# RJ45_Sheet.net
KiCad netlist of a schematic drawn in Altium Designer
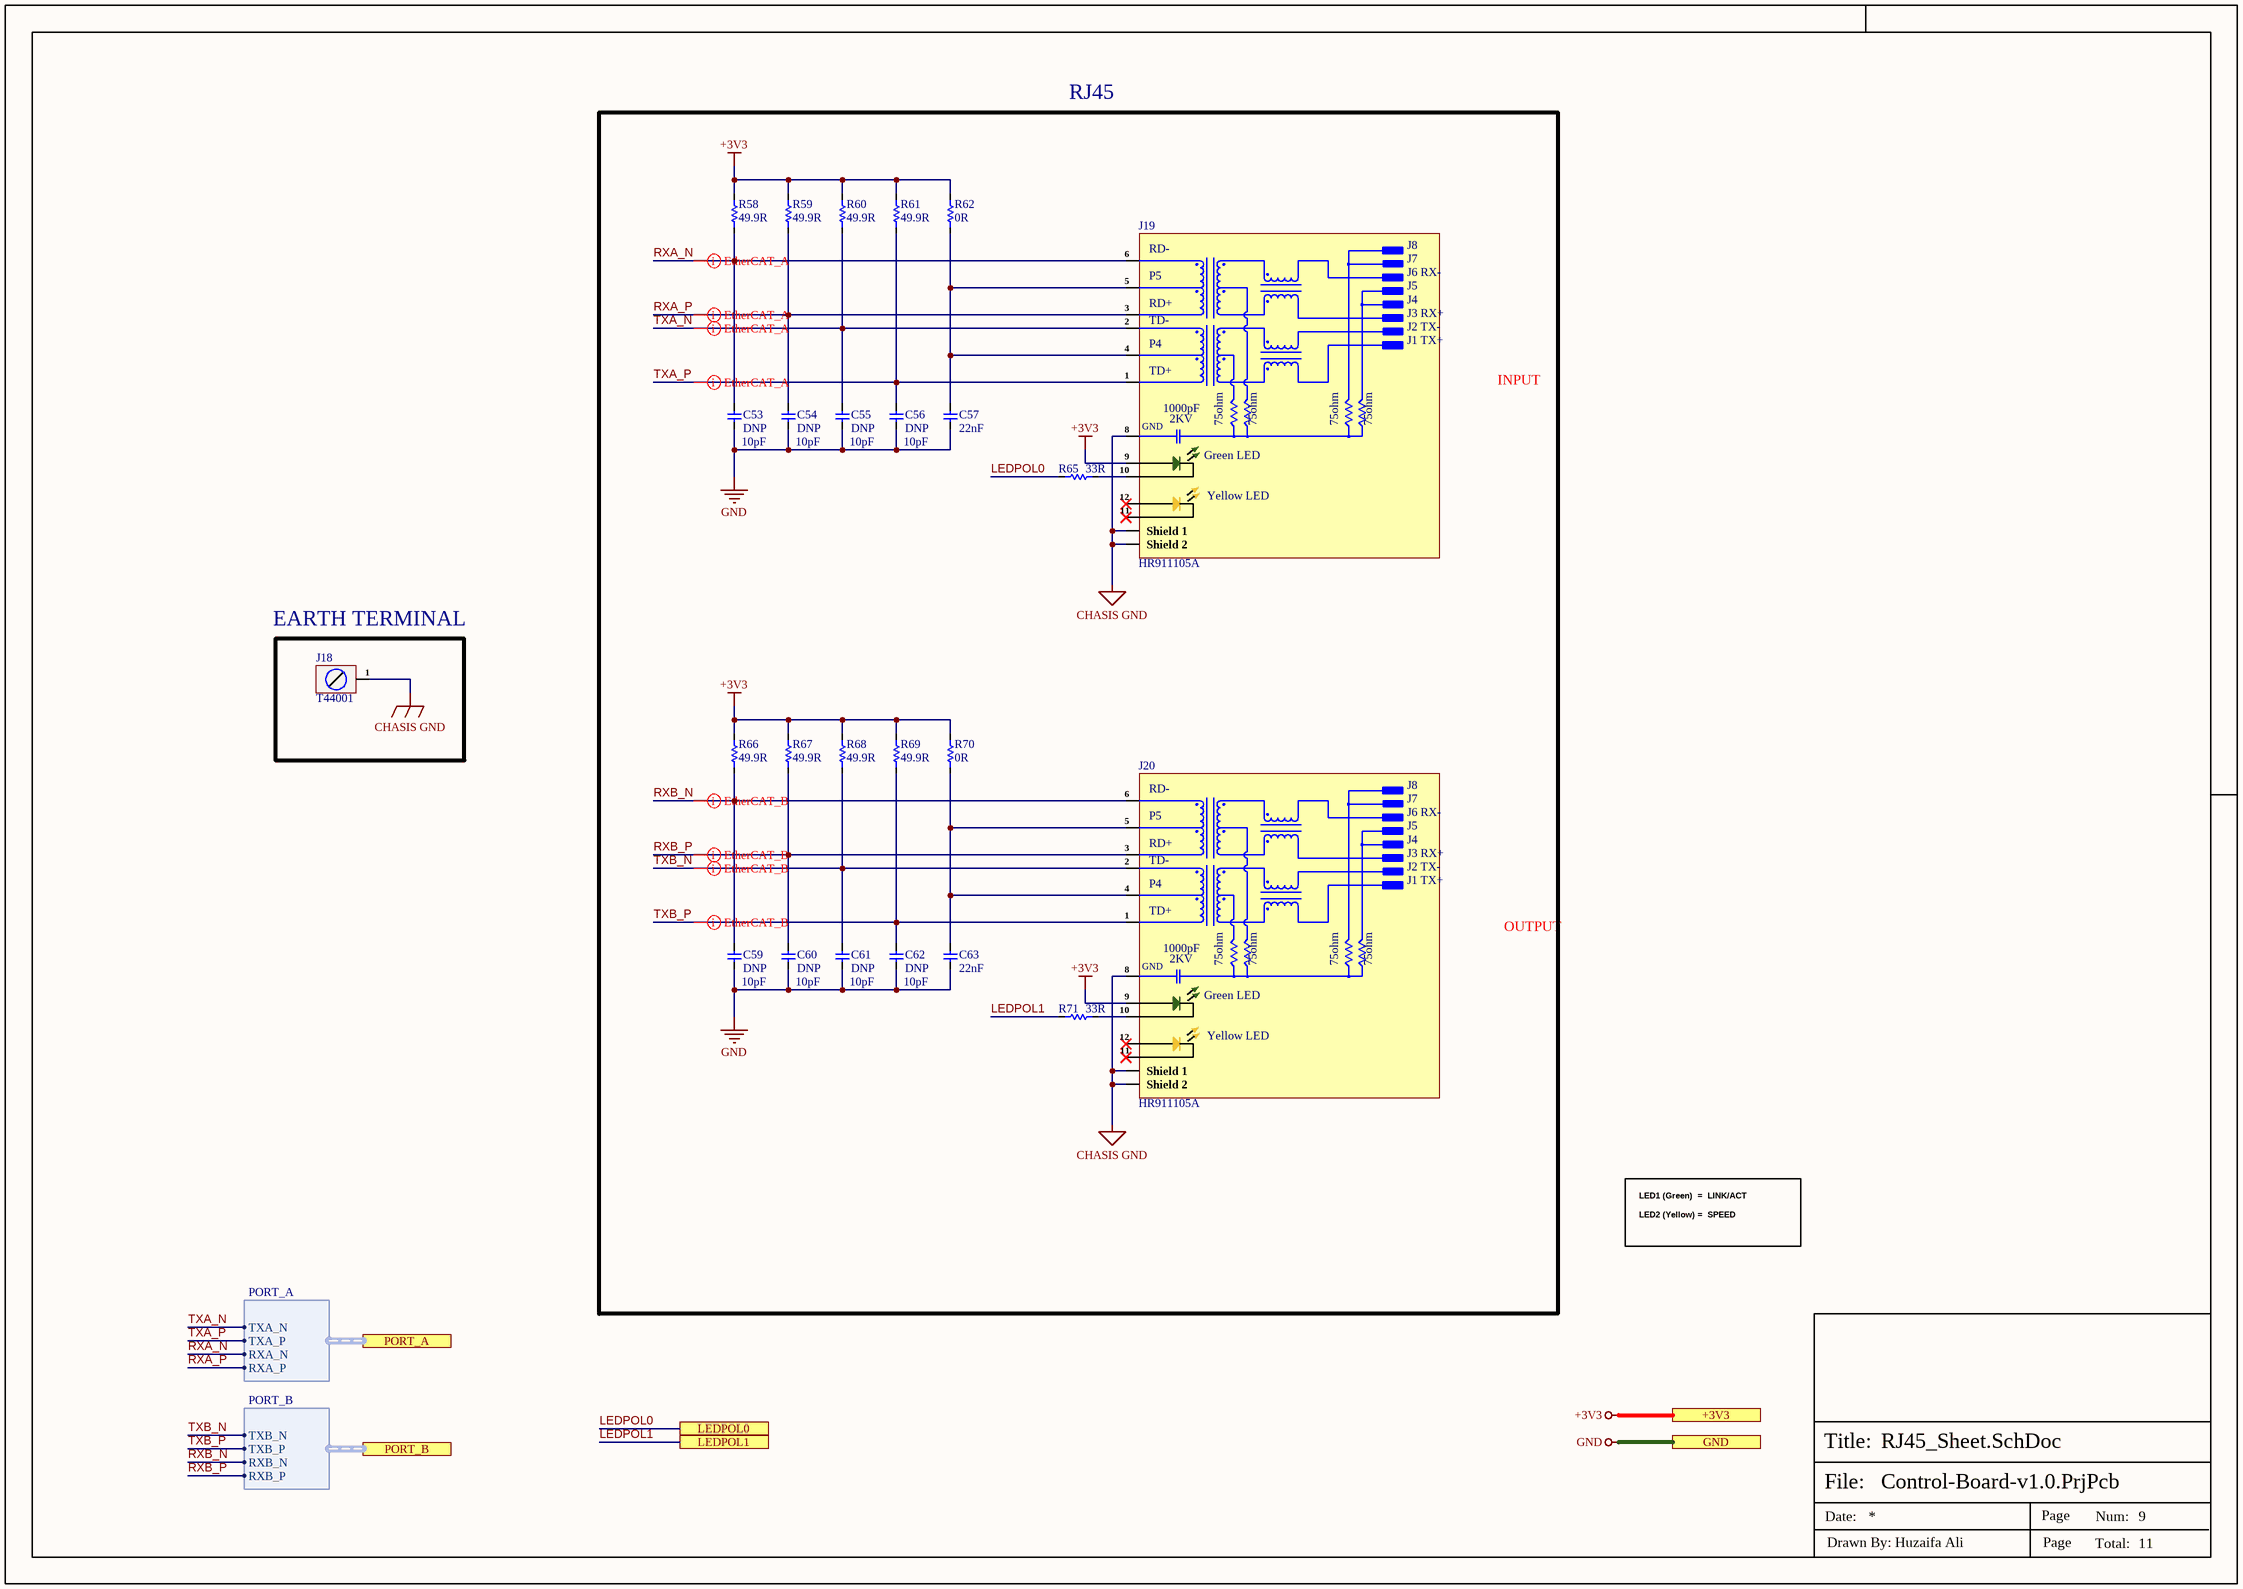
[diagram p0: RJ45_Sheet.SchDoc]

(export (version "E")
  (design (tool "Eeschema 10.0.6"))
  (components
    (comp (ref "C53")
      (value "DNP")
      (footprint "Cap-0402")
      (description "CAP CER 10PF 50V C0G/NP0 0402")
      (fields
        (field (name "MANUFACTURER") "Murata")
        (field (name "MANUFACTURER PART NUMBER") "GRM1555C1H100JA01D")
      )
      (libsource (lib "eSpark Libraries") (part "GRM1555C1H100JA01D"))
    )
    (comp (ref "C54")
      (value "DNP")
      (footprint "Cap-0402")
      (description "CAP CER 10PF 50V C0G/NP0 0402")
      (fields
        (field (name "MANUFACTURER") "Murata")
        (field (name "MANUFACTURER PART NUMBER") "GRM1555C1H100JA01D")
      )
      (libsource (lib "eSpark Libraries") (part "GRM1555C1H100JA01D"))
    )
    (comp (ref "C55")
      (value "DNP")
      (footprint "Cap-0402")
      (description "CAP CER 10PF 50V C0G/NP0 0402")
      (fields
        (field (name "MANUFACTURER") "Murata")
        (field (name "MANUFACTURER PART NUMBER") "GRM1555C1H100JA01D")
      )
      (libsource (lib "eSpark Libraries") (part "GRM1555C1H100JA01D"))
    )
    (comp (ref "C56")
      (value "DNP")
      (footprint "Cap-0402")
      (description "CAP CER 10PF 50V C0G/NP0 0402")
      (fields
        (field (name "MANUFACTURER") "Murata")
        (field (name "MANUFACTURER PART NUMBER") "GRM1555C1H100JA01D")
      )
      (libsource (lib "eSpark Libraries") (part "GRM1555C1H100JA01D"))
    )
    (comp (ref "C57")
      (value "22nF")
      (footprint "Cap-0402")
      (description "CAP CER 0.022UF 16V X7R 0402")
      (fields
        (field (name "MANUFACTURER") "Yageo")
        (field (name "MANUFACTURER PART NUMBER") "CC0402JRX7R7BB223")
      )
      (libsource (lib "eSpark Libraries") (part "CC0402JRX7R7BB223"))
    )
    (comp (ref "C59")
      (value "DNP")
      (footprint "Cap-0402")
      (description "CAP CER 10PF 50V C0G/NP0 0402")
      (fields
        (field (name "MANUFACTURER") "Murata")
        (field (name "MANUFACTURER PART NUMBER") "GRM1555C1H100JA01D")
      )
      (libsource (lib "eSpark Libraries") (part "GRM1555C1H100JA01D"))
    )
    (comp (ref "C60")
      (value "DNP")
      (footprint "Cap-0402")
      (description "CAP CER 10PF 50V C0G/NP0 0402")
      (fields
        (field (name "MANUFACTURER") "Murata")
        (field (name "MANUFACTURER PART NUMBER") "GRM1555C1H100JA01D")
      )
      (libsource (lib "eSpark Libraries") (part "GRM1555C1H100JA01D"))
    )
    (comp (ref "C61")
      (value "DNP")
      (footprint "Cap-0402")
      (description "CAP CER 10PF 50V C0G/NP0 0402")
      (fields
        (field (name "MANUFACTURER") "Murata")
        (field (name "MANUFACTURER PART NUMBER") "GRM1555C1H100JA01D")
      )
      (libsource (lib "eSpark Libraries") (part "GRM1555C1H100JA01D"))
    )
    (comp (ref "C62")
      (value "DNP")
      (footprint "Cap-0402")
      (description "CAP CER 10PF 50V C0G/NP0 0402")
      (fields
        (field (name "MANUFACTURER") "Murata")
        (field (name "MANUFACTURER PART NUMBER") "GRM1555C1H100JA01D")
      )
      (libsource (lib "eSpark Libraries") (part "GRM1555C1H100JA01D"))
    )
    (comp (ref "C63")
      (value "22nF")
      (footprint "Cap-0402")
      (description "CAP CER 0.022UF 16V X7R 0402")
      (fields
        (field (name "MANUFACTURER") "Yageo")
        (field (name "MANUFACTURER PART NUMBER") "CC0402JRX7R7BB223")
      )
      (libsource (lib "eSpark Libraries") (part "CC0402JRX7R7BB223"))
    )
    (comp (ref "J18")
      (value "T44001")
      (footprint "T44001")
      (description "M4 Plugin PCB Welding Terminal ROHS")
      (fields (field (name "MANUFACTURER") "XFCN"))
      (libsource (lib "eSpark Libraries") (part "T44001"))
    )
    (comp (ref "J19")
      (value "HR911105A")
      (footprint "HR911105A")
      (description "RJ45 RJReceptacle 1 WithLED Plugin Ethernet Connectors/Modular Connectors (RJ45 RJ11) ROHS")
      (fields (field (name "MANUFACTURER") "HANRUN") (field (name "LCSC PART NUMBER") "C12074"))
      (libsource (lib "eSpark Libraries") (part "HR911105A"))
    )
    (comp (ref "J20")
      (value "HR911105A")
      (footprint "HR911105A")
      (description "RJ45 RJReceptacle 1 WithLED Plugin Ethernet Connectors/Modular Connectors (RJ45 RJ11) ROHS")
      (fields (field (name "MANUFACTURER") "HANRUN") (field (name "LCSC PART NUMBER") "C12074"))
      (libsource (lib "eSpark Libraries") (part "HR911105A"))
    )
    (comp (ref "R58")
      (value "49.9R")
      (footprint "Res-0603")
      (description "RES 49.9 OHM 1% 1/10W 0603")
      (fields
        (field (name "MANUFACTURER") "Yageo")
        (field (name "MANUFACTURER PART NUMBER") "RC0603FR-0749R9L")
      )
      (libsource (lib "eSpark Libraries") (part "RC0603FR-0749R9L"))
    )
    (comp (ref "R59")
      (value "49.9R")
      (footprint "Res-0603")
      (description "RES 49.9 OHM 1% 1/10W 0603")
      (fields
        (field (name "MANUFACTURER") "Yageo")
        (field (name "MANUFACTURER PART NUMBER") "RC0603FR-0749R9L")
      )
      (libsource (lib "eSpark Libraries") (part "RC0603FR-0749R9L"))
    )
    (comp (ref "R60")
      (value "49.9R")
      (footprint "Res-0603")
      (description "RES 49.9 OHM 1% 1/10W 0603")
      (fields
        (field (name "MANUFACTURER") "Yageo")
        (field (name "MANUFACTURER PART NUMBER") "RC0603FR-0749R9L")
      )
      (libsource (lib "eSpark Libraries") (part "RC0603FR-0749R9L"))
    )
    (comp (ref "R61")
      (value "49.9R")
      (footprint "Res-0603")
      (description "RES 49.9 OHM 1% 1/10W 0603")
      (fields
        (field (name "MANUFACTURER") "Yageo")
        (field (name "MANUFACTURER PART NUMBER") "RC0603FR-0749R9L")
      )
      (libsource (lib "eSpark Libraries") (part "RC0603FR-0749R9L"))
    )
    (comp (ref "R62")
      (value "0R")
      (footprint "Res-0402")
      (description "RESISTOR 0402 JUMPER ZERO OHM")
      (fields
        (field (name "MANUFACTURER") "Yageo")
        (field (name "MANUFACTURER PART NUMBER") "AC0402FR-070RL")
      )
      (libsource (lib "eSpark Libraries") (part "AC0402FR-070RL"))
    )
    (comp (ref "R65")
      (value "33R")
      (footprint "Res-0402")
      (description "RES 33 OHM 1% 1/16W 0402")
      (fields
        (field (name "MANUFACTURER") "Yageo")
        (field (name "MANUFACTURER PART NUMBER") "RC0402FR-0733RL")
      )
      (libsource (lib "eSpark Libraries") (part "RC0402FR-0733RL"))
    )
    (comp (ref "R66")
      (value "49.9R")
      (footprint "Res-0603")
      (description "RES 49.9 OHM 1% 1/10W 0603")
      (fields
        (field (name "MANUFACTURER") "Yageo")
        (field (name "MANUFACTURER PART NUMBER") "RC0603FR-0749R9L")
      )
      (libsource (lib "eSpark Libraries") (part "RC0603FR-0749R9L"))
    )
    (comp (ref "R67")
      (value "49.9R")
      (footprint "Res-0603")
      (description "RES 49.9 OHM 1% 1/10W 0603")
      (fields
        (field (name "MANUFACTURER") "Yageo")
        (field (name "MANUFACTURER PART NUMBER") "RC0603FR-0749R9L")
      )
      (libsource (lib "eSpark Libraries") (part "RC0603FR-0749R9L"))
    )
    (comp (ref "R68")
      (value "49.9R")
      (footprint "Res-0603")
      (description "RES 49.9 OHM 1% 1/10W 0603")
      (fields
        (field (name "MANUFACTURER") "Yageo")
        (field (name "MANUFACTURER PART NUMBER") "RC0603FR-0749R9L")
      )
      (libsource (lib "eSpark Libraries") (part "RC0603FR-0749R9L"))
    )
    (comp (ref "R69")
      (value "49.9R")
      (footprint "Res-0603")
      (description "RES 49.9 OHM 1% 1/10W 0603")
      (fields
        (field (name "MANUFACTURER") "Yageo")
        (field (name "MANUFACTURER PART NUMBER") "RC0603FR-0749R9L")
      )
      (libsource (lib "eSpark Libraries") (part "RC0603FR-0749R9L"))
    )
    (comp (ref "R70")
      (value "0R")
      (footprint "Res-0402")
      (description "RESISTOR 0402 JUMPER ZERO OHM")
      (fields
        (field (name "MANUFACTURER") "Yageo")
        (field (name "MANUFACTURER PART NUMBER") "AC0402FR-070RL")
      )
      (libsource (lib "eSpark Libraries") (part "AC0402FR-070RL"))
    )
    (comp (ref "R71")
      (value "33R")
      (footprint "Res-0402")
      (description "RES 33 OHM 1% 1/16W 0402")
      (fields
        (field (name "MANUFACTURER") "Yageo")
        (field (name "MANUFACTURER PART NUMBER") "RC0402FR-0733RL")
      )
      (libsource (lib "eSpark Libraries") (part "RC0402FR-0733RL"))
    )
  )
  (nets
    (net (code "3") (name "+3V3") (class "Default")
      (node (ref "J19") (pin "9") (pinfunction "ANODE_9") (pintype "passive"))
      (node (ref "J20") (pin "9") (pinfunction "ANODE_9") (pintype "passive"))
      (node (ref "R58") (pin "2") (pinfunction "2_2") (pintype "passive"))
      (node (ref "R59") (pin "2") (pinfunction "2_2") (pintype "passive"))
      (node (ref "R60") (pin "2") (pinfunction "2_2") (pintype "passive"))
      (node (ref "R61") (pin "2") (pinfunction "2_2") (pintype "passive"))
      (node (ref "R62") (pin "2") (pinfunction "2_2") (pintype "passive"))
      (node (ref "R66") (pin "2") (pinfunction "2_2") (pintype "passive"))
      (node (ref "R67") (pin "2") (pinfunction "2_2") (pintype "passive"))
      (node (ref "R68") (pin "2") (pinfunction "2_2") (pintype "passive"))
      (node (ref "R69") (pin "2") (pinfunction "2_2") (pintype "passive"))
      (node (ref "R70") (pin "2") (pinfunction "2_2") (pintype "passive"))
    )
    (net (code "4") (name "/LEDPOL0") (class "Default")
      (node (ref "R65") (pin "1") (pinfunction "1_1") (pintype "passive"))
    )
    (net (code "5") (name "/LEDPOL1") (class "Default")
      (node (ref "R71") (pin "1") (pinfunction "1_1") (pintype "passive"))
    )
    (net (code "6") (name "/RXA_N") (class "Default")
      (node (ref "C53") (pin "2") (pinfunction "2_2") (pintype "passive"))
      (node (ref "J19") (pin "6") (pinfunction "RD-_6") (pintype "passive"))
      (node (ref "R58") (pin "1") (pinfunction "1_1") (pintype "passive"))
    )
    (net (code "7") (name "/RXA_P") (class "Default")
      (node (ref "C54") (pin "2") (pinfunction "2_2") (pintype "passive"))
      (node (ref "J19") (pin "3") (pinfunction "RD+_3") (pintype "passive"))
      (node (ref "R59") (pin "1") (pinfunction "1_1") (pintype "passive"))
    )
    (net (code "8") (name "/RXB_N") (class "Default")
      (node (ref "C59") (pin "2") (pinfunction "2_2") (pintype "passive"))
      (node (ref "J20") (pin "6") (pinfunction "RD-_6") (pintype "passive"))
      (node (ref "R66") (pin "1") (pinfunction "1_1") (pintype "passive"))
    )
    (net (code "9") (name "/RXB_P") (class "Default")
      (node (ref "C60") (pin "2") (pinfunction "2_2") (pintype "passive"))
      (node (ref "J20") (pin "3") (pinfunction "RD+_3") (pintype "passive"))
      (node (ref "R67") (pin "1") (pinfunction "1_1") (pintype "passive"))
    )
    (net (code "10") (name "/TXA_N") (class "Default")
      (node (ref "C55") (pin "2") (pinfunction "2_2") (pintype "passive"))
      (node (ref "J19") (pin "2") (pinfunction "TD-_2") (pintype "passive"))
      (node (ref "R60") (pin "1") (pinfunction "1_1") (pintype "passive"))
    )
    (net (code "11") (name "/TXA_P") (class "Default")
      (node (ref "C56") (pin "2") (pinfunction "2_2") (pintype "passive"))
      (node (ref "J19") (pin "1") (pinfunction "TD+_1") (pintype "passive"))
      (node (ref "R61") (pin "1") (pinfunction "1_1") (pintype "passive"))
    )
    (net (code "12") (name "/TXB_N") (class "Default")
      (node (ref "C61") (pin "2") (pinfunction "2_2") (pintype "passive"))
      (node (ref "J20") (pin "2") (pinfunction "TD-_2") (pintype "passive"))
      (node (ref "R68") (pin "1") (pinfunction "1_1") (pintype "passive"))
    )
    (net (code "13") (name "/TXB_P") (class "Default")
      (node (ref "C62") (pin "2") (pinfunction "2_2") (pintype "passive"))
      (node (ref "J20") (pin "1") (pinfunction "TD+_1") (pintype "passive"))
      (node (ref "R69") (pin "1") (pinfunction "1_1") (pintype "passive"))
    )
    (net (code "16") (name "CHASIS GND") (class "Default")
      (node (ref "J18") (pin "1") (pinfunction "1_1") (pintype "passive"))
      (node (ref "J19") (pin "8") (pinfunction "GND_8") (pintype "power_in"))
      (node (ref "J19") (pin "Shield_1") (pinfunction "Shield_1_Shield_1") (pintype "passive"))
      (node (ref "J19") (pin "Shield_2") (pinfunction "Shield_2_Shield_2") (pintype "passive"))
      (node (ref "J20") (pin "8") (pinfunction "GND_8") (pintype "power_in"))
      (node (ref "J20") (pin "Shield_1") (pinfunction "Shield_1_Shield_1") (pintype "passive"))
      (node (ref "J20") (pin "Shield_2") (pinfunction "Shield_2_Shield_2") (pintype "passive"))
    )
    (net (code "17") (name "GND") (class "Default")
      (node (ref "C53") (pin "1") (pinfunction "1_1") (pintype "passive"))
      (node (ref "C54") (pin "1") (pinfunction "1_1") (pintype "passive"))
      (node (ref "C55") (pin "1") (pinfunction "1_1") (pintype "passive"))
      (node (ref "C56") (pin "1") (pinfunction "1_1") (pintype "passive"))
      (node (ref "C57") (pin "1") (pinfunction "1_1") (pintype "passive"))
      (node (ref "C59") (pin "1") (pinfunction "1_1") (pintype "passive"))
      (node (ref "C60") (pin "1") (pinfunction "1_1") (pintype "passive"))
      (node (ref "C61") (pin "1") (pinfunction "1_1") (pintype "passive"))
      (node (ref "C62") (pin "1") (pinfunction "1_1") (pintype "passive"))
      (node (ref "C63") (pin "1") (pinfunction "1_1") (pintype "passive"))
    )
    (net (code "18") (name "Net-(J19-CATHODE-Pad10)") (class "Default")
      (node (ref "J19") (pin "10") (pinfunction "CATHODE_10") (pintype "passive"))
      (node (ref "R65") (pin "2") (pinfunction "2_2") (pintype "passive"))
    )
    (net (code "19") (name "Net-(J19-P4)") (class "Default")
      (node (ref "C57") (pin "2") (pinfunction "2_2") (pintype "passive"))
      (node (ref "J19") (pin "4") (pinfunction "P4_4") (pintype "passive"))
      (node (ref "J19") (pin "5") (pinfunction "P5_5") (pintype "passive"))
      (node (ref "R62") (pin "1") (pinfunction "1_1") (pintype "passive"))
    )
    (net (code "20") (name "Net-(J20-CATHODE-Pad10)") (class "Default")
      (node (ref "J20") (pin "10") (pinfunction "CATHODE_10") (pintype "passive"))
      (node (ref "R71") (pin "2") (pinfunction "2_2") (pintype "passive"))
    )
    (net (code "21") (name "Net-(J20-P4)") (class "Default")
      (node (ref "C63") (pin "2") (pinfunction "2_2") (pintype "passive"))
      (node (ref "J20") (pin "4") (pinfunction "P4_4") (pintype "passive"))
      (node (ref "J20") (pin "5") (pinfunction "P5_5") (pintype "passive"))
      (node (ref "R70") (pin "1") (pinfunction "1_1") (pintype "passive"))
    )
    (net (code "22") (name "unconnected-(J19-ANODE-Pad12)") (class "Default")
      (node (ref "J19") (pin "12") (pinfunction "ANODE_12") (pintype "passive+no_connect"))
    )
    (net (code "23") (name "unconnected-(J19-CATHODE-Pad11)") (class "Default")
      (node (ref "J19") (pin "11") (pinfunction "CATHODE_11") (pintype "passive+no_connect"))
    )
    (net (code "24") (name "unconnected-(J20-ANODE-Pad12)") (class "Default")
      (node (ref "J20") (pin "12") (pinfunction "ANODE_12") (pintype "passive+no_connect"))
    )
    (net (code "25") (name "unconnected-(J20-CATHODE-Pad11)") (class "Default")
      (node (ref "J20") (pin "11") (pinfunction "CATHODE_11") (pintype "passive+no_connect"))
    )
  )
)
